# ADC.net
KiCad netlist of a schematic drawn in EAGLE
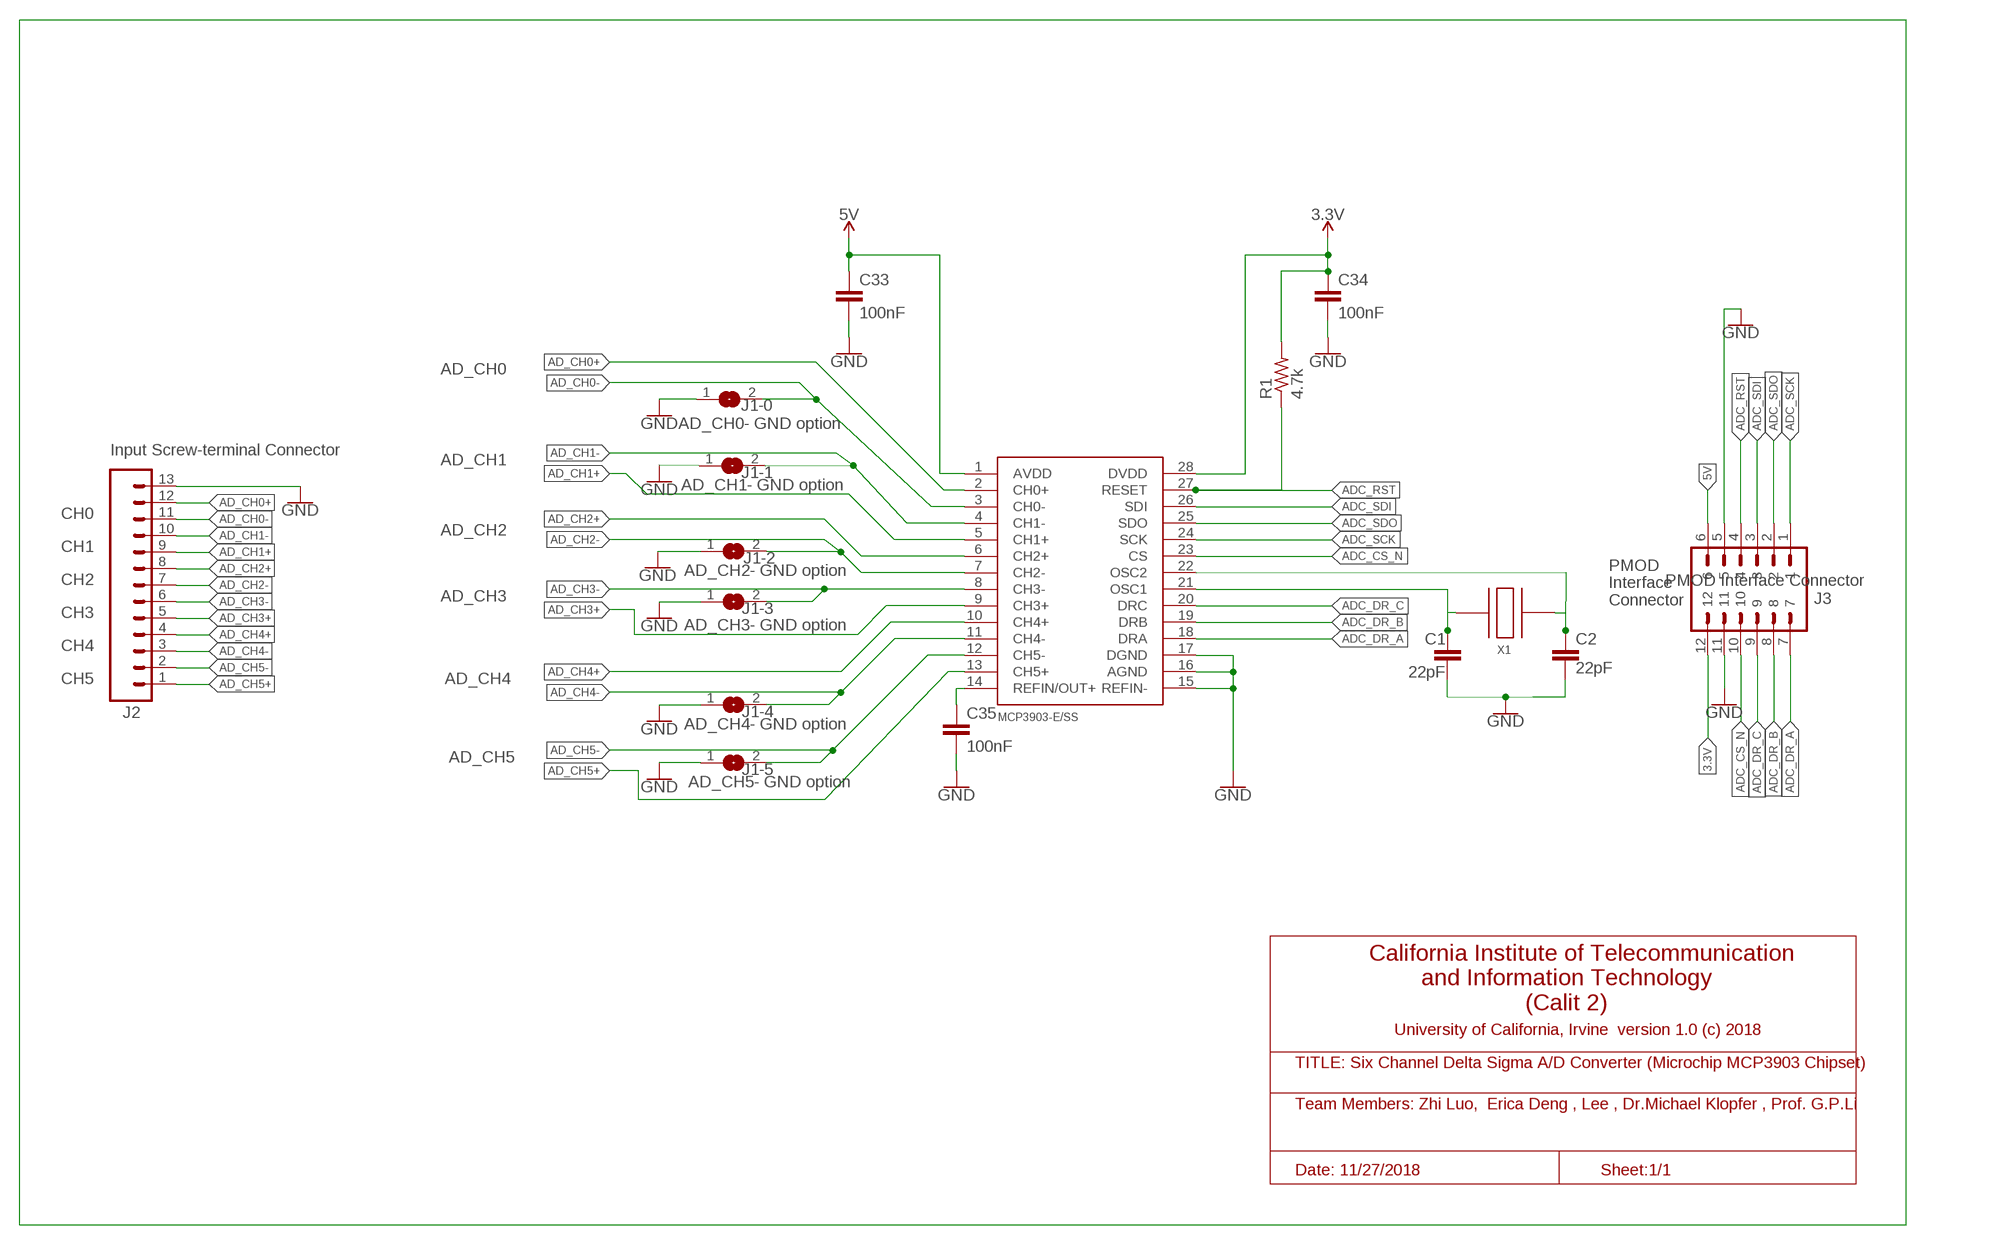
[diagram p0: schematic, sheet 1]

(export (version "E")
  (design (tool "Eeschema 10.0.6"))
  (components
    (comp (ref "C1")
      (value "22pF")
      (footprint "eagle-import:0603")
      (libsource (lib "eagle-import") (part "22PF-0603-50V-5%"))
    )
    (comp (ref "C2")
      (value "22pF")
      (footprint "eagle-import:0603")
      (libsource (lib "eagle-import") (part "22PF-0603-50V-5%"))
    )
    (comp (ref "C33")
      (value "100nF")
      (footprint "eagle-import:C0603")
      (libsource (lib "eagle-import") (part "CC0603"))
    )
    (comp (ref "C34")
      (value "100nF")
      (footprint "eagle-import:C0603")
      (libsource (lib "eagle-import") (part "CC0603"))
    )
    (comp (ref "C35")
      (value "100nF")
      (footprint "eagle-import:C0603")
      (libsource (lib "eagle-import") (part "CC0603"))
    )
    (comp (ref "J1-0")
      (value "AD_CH0- GND option")
      (footprint "eagle-import:SJ")
      (libsource (lib "eagle-import") (part "SJ"))
    )
    (comp (ref "J1-1")
      (value "AD_CH1- GND option")
      (footprint "eagle-import:SJ")
      (libsource (lib "eagle-import") (part "SJ"))
    )
    (comp (ref "J1-2")
      (value "AD_CH2- GND option")
      (footprint "eagle-import:SJ")
      (libsource (lib "eagle-import") (part "SJ"))
    )
    (comp (ref "J1-3")
      (value "AD_CH3- GND option")
      (footprint "eagle-import:SJ")
      (libsource (lib "eagle-import") (part "SJ"))
    )
    (comp (ref "J1-4")
      (value "AD_CH4- GND option")
      (footprint "eagle-import:SJ")
      (libsource (lib "eagle-import") (part "SJ"))
    )
    (comp (ref "J1-5")
      (value "AD_CH5- GND option")
      (footprint "eagle-import:SJ")
      (libsource (lib "eagle-import") (part "SJ"))
    )
    (comp (ref "J2")
      (value "Input Screw-terminal Connector")
      (footprint "eagle-import:1X13")
      (libsource (lib "eagle-import") (part "CONN_13"))
    )
    (comp (ref "J3")
      (value "PMOD Interface Connector")
      (footprint "eagle-import:2_6HEADER")
      (libsource (lib "eagle-import") (part "26HEADER"))
    )
    (comp (ref "R1")
      (value "4.7k")
      (footprint "eagle-import:0402-RES")
      (libsource (lib "eagle-import") (part "0402-RES"))
    )
    (comp (ref "U$1")
      (value "MCP3903")
      (footprint "eagle-import:28-LEADSSOP")
      (libsource (lib "eagle-import") (part "MCP3903"))
    )
    (comp (ref "X1")
      (value "4MHZ")
      (footprint "eagle-import:HC-49S")
      (libsource (lib "eagle-import") (part "QUARTZ_3.58M_2PIN"))
    )
  )
  (nets
    (net (code "1") (name "3.3V") (class "Default")
      (node (ref "C34") (pin "1") (pinfunction "1_1") (pintype "passive"))
      (node (ref "J3") (pin "12") (pinfunction "12_12") (pintype "passive"))
      (node (ref "R1") (pin "2") (pinfunction "2_2") (pintype "passive"))
      (node (ref "U$1") (pin "28") (pinfunction "DVDD_28") (pintype "bidirectional"))
    )
    (net (code "2") (name "5V") (class "Default")
      (node (ref "C33") (pin "1") (pinfunction "1_1") (pintype "passive"))
      (node (ref "J3") (pin "6") (pinfunction "6_6") (pintype "passive"))
      (node (ref "U$1") (pin "1") (pinfunction "AVDD_1") (pintype "bidirectional"))
    )
    (net (code "3") (name "ADC_CS_N") (class "Default")
      (node (ref "J3") (pin "10") (pinfunction "10_10") (pintype "passive"))
      (node (ref "U$1") (pin "23") (pinfunction "CS_23") (pintype "bidirectional"))
    )
    (net (code "4") (name "ADC_DR_A") (class "Default")
      (node (ref "J3") (pin "7") (pinfunction "7_7") (pintype "passive"))
      (node (ref "U$1") (pin "18") (pinfunction "DRA_18") (pintype "bidirectional"))
    )
    (net (code "5") (name "ADC_DR_B") (class "Default")
      (node (ref "J3") (pin "8") (pinfunction "8_8") (pintype "passive"))
      (node (ref "U$1") (pin "19") (pinfunction "DRB_19") (pintype "bidirectional"))
    )
    (net (code "6") (name "ADC_DR_C") (class "Default")
      (node (ref "J3") (pin "9") (pinfunction "9_9") (pintype "passive"))
      (node (ref "U$1") (pin "20") (pinfunction "DRC_20") (pintype "bidirectional"))
    )
    (net (code "7") (name "ADC_RST") (class "Default")
      (node (ref "J3") (pin "4") (pinfunction "4_4") (pintype "passive"))
      (node (ref "R1") (pin "1") (pinfunction "1_1") (pintype "passive"))
      (node (ref "U$1") (pin "27") (pinfunction "RESET_27") (pintype "bidirectional"))
    )
    (net (code "8") (name "ADC_SCK") (class "Default")
      (node (ref "J3") (pin "1") (pinfunction "1_1") (pintype "passive"))
      (node (ref "U$1") (pin "24") (pinfunction "SCK_24") (pintype "bidirectional"))
    )
    (net (code "9") (name "ADC_SDI") (class "Default")
      (node (ref "J3") (pin "3") (pinfunction "3_3") (pintype "passive"))
      (node (ref "U$1") (pin "26") (pinfunction "SDI_26") (pintype "bidirectional"))
    )
    (net (code "10") (name "ADC_SDO") (class "Default")
      (node (ref "J3") (pin "2") (pinfunction "2_2") (pintype "passive"))
      (node (ref "U$1") (pin "25") (pinfunction "SDO_25") (pintype "bidirectional"))
    )
    (net (code "11") (name "AD_CH0+") (class "Default")
      (node (ref "J2") (pin "12") (pinfunction "12_12") (pintype "passive"))
      (node (ref "U$1") (pin "2") (pinfunction "CH0+_2") (pintype "bidirectional"))
    )
    (net (code "12") (name "AD_CH0-") (class "Default")
      (node (ref "J1-0") (pin "2") (pinfunction "2_2") (pintype "passive"))
      (node (ref "J2") (pin "11") (pinfunction "11_11") (pintype "passive"))
      (node (ref "U$1") (pin "3") (pinfunction "CH0-_3") (pintype "bidirectional"))
    )
    (net (code "13") (name "AD_CH1+") (class "Default")
      (node (ref "J2") (pin "9") (pinfunction "9_9") (pintype "passive"))
      (node (ref "U$1") (pin "5") (pinfunction "CH1+_5") (pintype "bidirectional"))
    )
    (net (code "14") (name "AD_CH1-") (class "Default")
      (node (ref "J1-1") (pin "2") (pinfunction "2_2") (pintype "passive"))
      (node (ref "J2") (pin "10") (pinfunction "10_10") (pintype "passive"))
      (node (ref "U$1") (pin "4") (pinfunction "CH1-_4") (pintype "bidirectional"))
    )
    (net (code "15") (name "AD_CH2+") (class "Default")
      (node (ref "J2") (pin "8") (pinfunction "8_8") (pintype "passive"))
      (node (ref "U$1") (pin "6") (pinfunction "CH2+_6") (pintype "bidirectional"))
    )
    (net (code "16") (name "AD_CH2-") (class "Default")
      (node (ref "J1-2") (pin "2") (pinfunction "2_2") (pintype "passive"))
      (node (ref "J2") (pin "7") (pinfunction "7_7") (pintype "passive"))
      (node (ref "U$1") (pin "7") (pinfunction "CH2-_7") (pintype "bidirectional"))
    )
    (net (code "17") (name "AD_CH3+") (class "Default")
      (node (ref "J2") (pin "5") (pinfunction "5_5") (pintype "passive"))
      (node (ref "U$1") (pin "9") (pinfunction "CH3+_9") (pintype "bidirectional"))
    )
    (net (code "18") (name "AD_CH3-") (class "Default")
      (node (ref "J1-3") (pin "2") (pinfunction "2_2") (pintype "passive"))
      (node (ref "J2") (pin "6") (pinfunction "6_6") (pintype "passive"))
      (node (ref "U$1") (pin "8") (pinfunction "CH3-_8") (pintype "bidirectional"))
    )
    (net (code "19") (name "AD_CH4+") (class "Default")
      (node (ref "J2") (pin "4") (pinfunction "4_4") (pintype "passive"))
      (node (ref "U$1") (pin "10") (pinfunction "CH4+_10") (pintype "bidirectional"))
    )
    (net (code "20") (name "AD_CH4-") (class "Default")
      (node (ref "J1-4") (pin "2") (pinfunction "2_2") (pintype "passive"))
      (node (ref "J2") (pin "3") (pinfunction "3_3") (pintype "passive"))
      (node (ref "U$1") (pin "11") (pinfunction "CH4-_11") (pintype "bidirectional"))
    )
    (net (code "21") (name "AD_CH5+") (class "Default")
      (node (ref "J2") (pin "1") (pinfunction "1_1") (pintype "passive"))
      (node (ref "U$1") (pin "13") (pinfunction "CH5+_13") (pintype "bidirectional"))
    )
    (net (code "22") (name "AD_CH5-") (class "Default")
      (node (ref "J1-5") (pin "2") (pinfunction "2_2") (pintype "passive"))
      (node (ref "J2") (pin "2") (pinfunction "2_2") (pintype "passive"))
      (node (ref "U$1") (pin "12") (pinfunction "CH5-_12") (pintype "bidirectional"))
    )
    (net (code "23") (name "GND") (class "Default")
      (node (ref "C1") (pin "2") (pinfunction "2_2") (pintype "passive"))
      (node (ref "C33") (pin "2") (pinfunction "2_2") (pintype "passive"))
      (node (ref "C34") (pin "2") (pinfunction "2_2") (pintype "passive"))
      (node (ref "C35") (pin "2") (pinfunction "2_2") (pintype "passive"))
      (node (ref "J1-0") (pin "1") (pinfunction "1_1") (pintype "passive"))
      (node (ref "J1-1") (pin "1") (pinfunction "1_1") (pintype "passive"))
      (node (ref "J1-2") (pin "1") (pinfunction "1_1") (pintype "passive"))
      (node (ref "J1-3") (pin "1") (pinfunction "1_1") (pintype "passive"))
      (node (ref "J1-4") (pin "1") (pinfunction "1_1") (pintype "passive"))
      (node (ref "J1-5") (pin "1") (pinfunction "1_1") (pintype "passive"))
      (node (ref "J2") (pin "13") (pinfunction "13_13") (pintype "passive"))
      (node (ref "J3") (pin "11") (pinfunction "11_11") (pintype "passive"))
      (node (ref "J3") (pin "5") (pinfunction "5_5") (pintype "passive"))
      (node (ref "U$1") (pin "15") (pinfunction "REFIN-_15") (pintype "bidirectional"))
      (node (ref "U$1") (pin "16") (pinfunction "AGND_16") (pintype "bidirectional"))
      (node (ref "U$1") (pin "17") (pinfunction "DGND_17") (pintype "bidirectional"))
    )
    (net (code "24") (name "Net-(U$1-OSC1)") (class "Default")
      (node (ref "C1") (pin "1") (pinfunction "1_1") (pintype "passive"))
      (node (ref "U$1") (pin "21") (pinfunction "OSC1_21") (pintype "bidirectional"))
      (node (ref "X1") (pin "1") (pinfunction "1_1") (pintype "bidirectional"))
    )
    (net (code "25") (name "Net-(U$1-OSC2)") (class "Default")
      (node (ref "C2") (pin "1") (pinfunction "1_1") (pintype "passive"))
      (node (ref "U$1") (pin "22") (pinfunction "OSC2_22") (pintype "bidirectional"))
      (node (ref "X1") (pin "2") (pinfunction "2_2") (pintype "bidirectional"))
    )
    (net (code "26") (name "Net-(U$1-REFIN{slash}OUT+)") (class "Default")
      (node (ref "C35") (pin "1") (pinfunction "1_1") (pintype "passive"))
      (node (ref "U$1") (pin "14") (pinfunction "REFIN/OUT+_14") (pintype "bidirectional"))
    )
    (net (code "27") (name "unconnected-(C2-Pad2)") (class "Default")
      (node (ref "C2") (pin "2") (pinfunction "2_2") (pintype "passive"))
    )
  )
)
